# Sheet2.net
KiCad netlist of a schematic drawn in Altium Designer
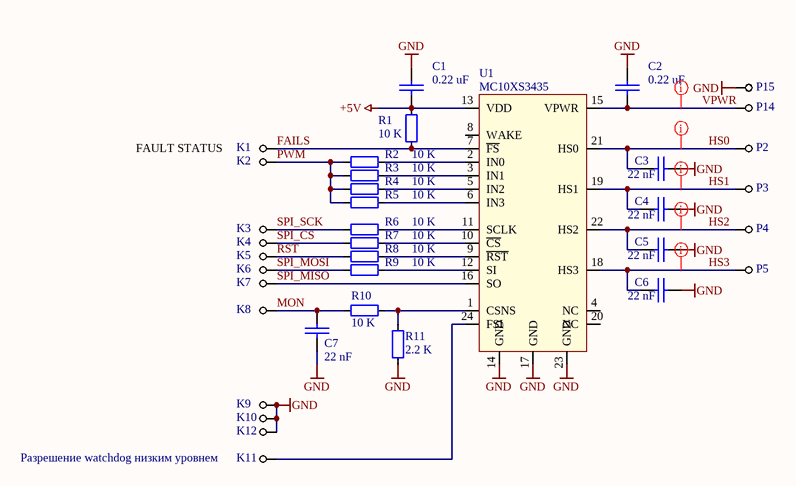
[diagram p0: Sheet2.SchDoc]

(export (version "E")
  (design (tool "Eeschema 10.0.6"))
  (components
    (comp (ref "C1")
      (value "0.22 uF")
      (footprint "2012[0805]")
      (description "0.22 uF, 50V, X7R,  0805")
      (fields (field (name "TOLERANCE") "+-10%") (field (name "MANUFACTURER") "Kemet"))
      (libsource (lib "ea_Capacitors") (part "C0805C224K5RACTU"))
    )
    (comp (ref "C2")
      (value "0.22 uF")
      (footprint "2012[0805]")
      (description "0.22 uF, 50V, X7R,  0805")
      (fields (field (name "TOLERANCE") "+-10%") (field (name "MANUFACTURER") "Kemet"))
      (libsource (lib "ea_Capacitors") (part "C0805C224K5RACTU"))
    )
    (comp (ref "C3")
      (value "22 nF")
      (footprint "1608[0603]")
      (description "22 nF, 50V, 10%, X7R, 0603 SMD MLC Capacitor")
      (fields (field (name "TOLERANCE") "10%") (field (name "MANUFACTURER") "SAMSUNG"))
      (libsource (lib "ea_Capacitors") (part "CL10B223KB8NNNC"))
    )
    (comp (ref "C4")
      (value "22 nF")
      (footprint "1608[0603]")
      (description "22 nF, 50V, 10%, X7R, 0603 SMD MLC Capacitor")
      (fields (field (name "TOLERANCE") "10%") (field (name "MANUFACTURER") "SAMSUNG"))
      (libsource (lib "ea_Capacitors") (part "CL10B223KB8NNNC"))
    )
    (comp (ref "C5")
      (value "22 nF")
      (footprint "1608[0603]")
      (description "22 nF, 50V, 10%, X7R, 0603 SMD MLC Capacitor")
      (fields (field (name "TOLERANCE") "10%") (field (name "MANUFACTURER") "SAMSUNG"))
      (libsource (lib "ea_Capacitors") (part "CL10B223KB8NNNC"))
    )
    (comp (ref "C6")
      (value "22 nF")
      (footprint "1608[0603]")
      (description "22 nF, 50V, 10%, X7R, 0603 SMD MLC Capacitor")
      (fields (field (name "TOLERANCE") "10%") (field (name "MANUFACTURER") "SAMSUNG"))
      (libsource (lib "ea_Capacitors") (part "CL10B223KB8NNNC"))
    )
    (comp (ref "C7")
      (value "22 nF")
      (footprint "1608[0603]")
      (description "22 nF, 50V, 10%, X7R, 0603 SMD MLC Capacitor")
      (fields (field (name "TOLERANCE") "10%") (field (name "MANUFACTURER") "SAMSUNG"))
      (libsource (lib "ea_Capacitors") (part "CL10B223KB8NNNC"))
    )
    (comp (ref "K1")
      (value "Pin 0.7 mm")
      (footprint "Mount hole 0.7 mm")
      (libsource (lib "ea_Connectors") (part "Pin 0.7 mm"))
    )
    (comp (ref "K2")
      (value "Pin 0.7 mm")
      (footprint "Mount hole 0.7 mm")
      (libsource (lib "ea_Connectors") (part "Pin 0.7 mm"))
    )
    (comp (ref "K3")
      (value "Pin 0.7 mm")
      (footprint "Mount hole 0.7 mm")
      (libsource (lib "ea_Connectors") (part "Pin 0.7 mm"))
    )
    (comp (ref "K4")
      (value "Pin 0.7 mm")
      (footprint "Mount hole 0.7 mm")
      (libsource (lib "ea_Connectors") (part "Pin 0.7 mm"))
    )
    (comp (ref "K5")
      (value "Pin 0.7 mm")
      (footprint "Mount hole 0.7 mm")
      (libsource (lib "ea_Connectors") (part "Pin 0.7 mm"))
    )
    (comp (ref "K6")
      (value "Pin 0.7 mm")
      (footprint "Mount hole 0.7 mm")
      (libsource (lib "ea_Connectors") (part "Pin 0.7 mm"))
    )
    (comp (ref "K7")
      (value "Pin 0.7 mm")
      (footprint "Mount hole 0.7 mm")
      (libsource (lib "ea_Connectors") (part "Pin 0.7 mm"))
    )
    (comp (ref "K8")
      (value "Pin 0.7 mm")
      (footprint "Mount hole 0.7 mm")
      (libsource (lib "ea_Connectors") (part "Pin 0.7 mm"))
    )
    (comp (ref "K9")
      (value "Pin 0.7 mm")
      (footprint "Mount hole 0.7 mm")
      (libsource (lib "ea_Connectors") (part "Pin 0.7 mm"))
    )
    (comp (ref "K10")
      (value "Pin 0.7 mm")
      (footprint "Mount hole 0.7 mm")
      (libsource (lib "ea_Connectors") (part "Pin 0.7 mm"))
    )
    (comp (ref "K11")
      (value "Pin 0.7 mm")
      (footprint "Mount hole 0.7 mm")
      (libsource (lib "ea_Connectors") (part "Pin 0.7 mm"))
    )
    (comp (ref "K12")
      (value "Pin 0.7 mm")
      (footprint "Mount hole 0.7 mm")
      (libsource (lib "ea_Connectors") (part "Pin 0.7 mm"))
    )
    (comp (ref "P2")
      (value "Pin 0.7 mm")
      (footprint "Mount hole 0.7 mm")
      (libsource (lib "ea_Connectors") (part "Pin 0.7 mm"))
    )
    (comp (ref "P3")
      (value "Pin 0.7 mm")
      (footprint "Mount hole 0.7 mm")
      (libsource (lib "ea_Connectors") (part "Pin 0.7 mm"))
    )
    (comp (ref "P4")
      (value "Pin 0.7 mm")
      (footprint "Mount hole 0.7 mm")
      (libsource (lib "ea_Connectors") (part "Pin 0.7 mm"))
    )
    (comp (ref "P5")
      (value "Pin 0.7 mm")
      (footprint "Mount hole 0.7 mm")
      (libsource (lib "ea_Connectors") (part "Pin 0.7 mm"))
    )
    (comp (ref "P14")
      (value "Pin 0.7 mm")
      (footprint "Mount hole 0.7 mm")
      (libsource (lib "ea_Connectors") (part "Pin 0.7 mm"))
    )
    (comp (ref "P15")
      (value "Pin 0.7 mm")
      (footprint "Mount hole 0.7 mm")
      (libsource (lib "ea_Connectors") (part "Pin 0.7 mm"))
    )
    (comp (ref "R1")
      (value "10 K")
      (footprint "0603")
      (description "10 K, 1%, 0603, SMD Resistor, Taped")
      (fields (field (name "MANUFACTURER") "PANASONIC") (field (name "TOLERANCE") "1%"))
      (libsource (lib "") (part "RL0603K010-1_1_1"))
    )
    (comp (ref "R2")
      (value "10 K")
      (footprint "0603")
      (description "10 K, 1%, 0603, SMD Resistor, Taped")
      (fields (field (name "MANUFACTURER") "PANASONIC") (field (name "TOLERANCE") "1%"))
      (libsource (lib "ea_Resistors") (part "RL0603K010-1_1"))
    )
    (comp (ref "R3")
      (value "10 K")
      (footprint "0603")
      (description "10 K, 1%, 0603, SMD Resistor, Taped")
      (fields (field (name "MANUFACTURER") "PANASONIC") (field (name "TOLERANCE") "1%"))
      (libsource (lib "ea_Resistors") (part "RL0603K010-1_1"))
    )
    (comp (ref "R4")
      (value "10 K")
      (footprint "0603")
      (description "10 K, 1%, 0603, SMD Resistor, Taped")
      (fields (field (name "MANUFACTURER") "PANASONIC") (field (name "TOLERANCE") "1%"))
      (libsource (lib "ea_Resistors") (part "RL0603K010-1_1"))
    )
    (comp (ref "R5")
      (value "10 K")
      (footprint "0603")
      (description "10 K, 1%, 0603, SMD Resistor, Taped")
      (fields (field (name "MANUFACTURER") "PANASONIC") (field (name "TOLERANCE") "1%"))
      (libsource (lib "ea_Resistors") (part "RL0603K010-1_1"))
    )
    (comp (ref "R6")
      (value "10 K")
      (footprint "0603")
      (description "10 K, 1%, 0603, SMD Resistor, Taped")
      (fields (field (name "MANUFACTURER") "PANASONIC") (field (name "TOLERANCE") "1%"))
      (libsource (lib "ea_Resistors") (part "RL0603K010-1_1"))
    )
    (comp (ref "R7")
      (value "10 K")
      (footprint "0603")
      (description "10 K, 1%, 0603, SMD Resistor, Taped")
      (fields (field (name "MANUFACTURER") "PANASONIC") (field (name "TOLERANCE") "1%"))
      (libsource (lib "ea_Resistors") (part "RL0603K010-1_1"))
    )
    (comp (ref "R8")
      (value "10 K")
      (footprint "0603")
      (description "10 K, 1%, 0603, SMD Resistor, Taped")
      (fields (field (name "MANUFACTURER") "PANASONIC") (field (name "TOLERANCE") "1%"))
      (libsource (lib "ea_Resistors") (part "RL0603K010-1_1"))
    )
    (comp (ref "R9")
      (value "10 K")
      (footprint "0603")
      (description "10 K, 1%, 0603, SMD Resistor, Taped")
      (fields (field (name "MANUFACTURER") "PANASONIC") (field (name "TOLERANCE") "1%"))
      (libsource (lib "ea_Resistors") (part "RL0603K010-1_1"))
    )
    (comp (ref "R10")
      (value "10 K")
      (footprint "0603")
      (description "10 K, 1%, 0603, SMD Resistor, Taped")
      (fields (field (name "MANUFACTURER") "PANASONIC") (field (name "TOLERANCE") "1%"))
      (libsource (lib "ea_Resistors") (part "RL0603K010-1_1"))
    )
    (comp (ref "R11")
      (value "2.2 K")
      (footprint "0603")
      (description "2.2 K, 1%, 0603, SMD Resistor, Taped")
      (fields (field (name "MANUFACTURER") "YAGEO AMERICA CORPORATION") (field (name "TOLERANCE") "1%"))
      (libsource (lib "ea_Resistors") (part "RL0603K002.2-1_1"))
    )
    (comp (ref "U1")
      (value "MC10XS3435")
      (footprint "24-PIN PQFN (12*12)")
      (description "Quad High-side Switch, -40..+125C, 24 PQFN")
      (fields (field (name "MANUFACTURER") "Freescale"))
      (libsource (lib "ea_IC_Interfaces") (part "MC10XS3435"))
    )
  )
  (nets
    (net (code "1") (name "+5V") (class "Default")
      (node (ref "C1") (pin "2") (pinfunction "2_2") (pintype "passive"))
      (node (ref "R1") (pin "1") (pinfunction "1_1") (pintype "passive"))
      (node (ref "U1") (pin "13") (pinfunction "VDD_13") (pintype "passive"))
    )
    (net (code "2") (name "/FAILS") (class "Default")
      (node (ref "K1") (pin "1") (pinfunction "1_1") (pintype "passive"))
      (node (ref "R1") (pin "2") (pinfunction "2_2") (pintype "passive"))
      (node (ref "U1") (pin "7") (pinfunction "~{FS}_7") (pintype "passive"))
    )
    (net (code "3") (name "/HS0") (class "Default")
      (node (ref "C3") (pin "1") (pinfunction "1_1") (pintype "passive"))
      (node (ref "P2") (pin "1") (pinfunction "1_1") (pintype "passive"))
      (node (ref "U1") (pin "21") (pinfunction "HS0_21") (pintype "passive"))
    )
    (net (code "4") (name "/HS1") (class "Default")
      (node (ref "C4") (pin "1") (pinfunction "1_1") (pintype "passive"))
      (node (ref "P3") (pin "1") (pinfunction "1_1") (pintype "passive"))
      (node (ref "U1") (pin "19") (pinfunction "HS1_19") (pintype "passive"))
    )
    (net (code "5") (name "/HS2") (class "Default")
      (node (ref "C5") (pin "1") (pinfunction "1_1") (pintype "passive"))
      (node (ref "P4") (pin "1") (pinfunction "1_1") (pintype "passive"))
      (node (ref "U1") (pin "22") (pinfunction "HS2_22") (pintype "passive"))
    )
    (net (code "6") (name "/HS3") (class "Default")
      (node (ref "C6") (pin "1") (pinfunction "1_1") (pintype "passive"))
      (node (ref "P5") (pin "1") (pinfunction "1_1") (pintype "passive"))
      (node (ref "U1") (pin "18") (pinfunction "HS3_18") (pintype "passive"))
    )
    (net (code "7") (name "/MON") (class "Default")
      (node (ref "C7") (pin "1") (pinfunction "1_1") (pintype "passive"))
      (node (ref "K8") (pin "1") (pinfunction "1_1") (pintype "passive"))
      (node (ref "R10") (pin "2") (pinfunction "2_2") (pintype "passive"))
    )
    (net (code "8") (name "/PWM") (class "Default")
      (node (ref "K2") (pin "1") (pinfunction "1_1") (pintype "passive"))
      (node (ref "R2") (pin "2") (pinfunction "2_2") (pintype "passive"))
      (node (ref "R3") (pin "2") (pinfunction "2_2") (pintype "passive"))
      (node (ref "R4") (pin "2") (pinfunction "2_2") (pintype "passive"))
      (node (ref "R5") (pin "2") (pinfunction "2_2") (pintype "passive"))
    )
    (net (code "9") (name "/RST") (class "Default")
      (node (ref "K5") (pin "1") (pinfunction "1_1") (pintype "passive"))
      (node (ref "R8") (pin "2") (pinfunction "2_2") (pintype "passive"))
    )
    (net (code "10") (name "/SPI_CS") (class "Default")
      (node (ref "K4") (pin "1") (pinfunction "1_1") (pintype "passive"))
      (node (ref "R7") (pin "2") (pinfunction "2_2") (pintype "passive"))
    )
    (net (code "11") (name "/SPI_MISO") (class "Default")
      (node (ref "K7") (pin "1") (pinfunction "1_1") (pintype "passive"))
      (node (ref "U1") (pin "16") (pinfunction "SO_16") (pintype "passive"))
    )
    (net (code "12") (name "/SPI_MOSI") (class "Default")
      (node (ref "K6") (pin "1") (pinfunction "1_1") (pintype "passive"))
      (node (ref "R9") (pin "2") (pinfunction "2_2") (pintype "passive"))
    )
    (net (code "13") (name "/SPI_SCK") (class "Default")
      (node (ref "K3") (pin "1") (pinfunction "1_1") (pintype "passive"))
      (node (ref "R6") (pin "2") (pinfunction "2_2") (pintype "passive"))
    )
    (net (code "14") (name "/VPWR") (class "Default")
      (node (ref "C2") (pin "2") (pinfunction "2_2") (pintype "passive"))
      (node (ref "P14") (pin "1") (pinfunction "1_1") (pintype "passive"))
      (node (ref "U1") (pin "15") (pinfunction "VPWR_15") (pintype "passive"))
    )
    (net (code "15") (name "GND") (class "Default")
      (node (ref "C1") (pin "1") (pinfunction "1_1") (pintype "passive"))
      (node (ref "C2") (pin "1") (pinfunction "1_1") (pintype "passive"))
      (node (ref "C3") (pin "2") (pinfunction "2_2") (pintype "passive"))
      (node (ref "C4") (pin "2") (pinfunction "2_2") (pintype "passive"))
      (node (ref "C5") (pin "2") (pinfunction "2_2") (pintype "passive"))
      (node (ref "C6") (pin "2") (pinfunction "2_2") (pintype "passive"))
      (node (ref "C7") (pin "2") (pinfunction "2_2") (pintype "passive"))
      (node (ref "K10") (pin "1") (pinfunction "1_1") (pintype "passive"))
      (node (ref "K12") (pin "1") (pinfunction "1_1") (pintype "passive"))
      (node (ref "K9") (pin "1") (pinfunction "1_1") (pintype "passive"))
      (node (ref "P15") (pin "1") (pinfunction "1_1") (pintype "passive"))
      (node (ref "R11") (pin "2") (pinfunction "2_2") (pintype "passive"))
      (node (ref "U1") (pin "14") (pinfunction "GND_14") (pintype "passive"))
      (node (ref "U1") (pin "17") (pinfunction "GND_17") (pintype "passive"))
      (node (ref "U1") (pin "23") (pinfunction "GND_23") (pintype "passive"))
    )
    (net (code "16") (name "Net-(U1-CSNS)") (class "Default")
      (node (ref "R10") (pin "1") (pinfunction "1_1") (pintype "passive"))
      (node (ref "R11") (pin "1") (pinfunction "1_1") (pintype "passive"))
      (node (ref "U1") (pin "1") (pinfunction "CSNS_1") (pintype "passive"))
    )
    (net (code "17") (name "Net-(U1-FSI)") (class "Default")
      (node (ref "K11") (pin "1") (pinfunction "1_1") (pintype "passive"))
      (node (ref "U1") (pin "24") (pinfunction "FSI_24") (pintype "passive"))
    )
    (net (code "18") (name "Net-(U1-IN0)") (class "Default")
      (node (ref "R2") (pin "1") (pinfunction "1_1") (pintype "passive"))
      (node (ref "U1") (pin "2") (pinfunction "IN0_2") (pintype "passive"))
    )
    (net (code "19") (name "Net-(U1-IN1)") (class "Default")
      (node (ref "R3") (pin "1") (pinfunction "1_1") (pintype "passive"))
      (node (ref "U1") (pin "3") (pinfunction "IN1_3") (pintype "passive"))
    )
    (net (code "20") (name "Net-(U1-IN2)") (class "Default")
      (node (ref "R4") (pin "1") (pinfunction "1_1") (pintype "passive"))
      (node (ref "U1") (pin "5") (pinfunction "IN2_5") (pintype "passive"))
    )
    (net (code "21") (name "Net-(U1-IN3)") (class "Default")
      (node (ref "R5") (pin "1") (pinfunction "1_1") (pintype "passive"))
      (node (ref "U1") (pin "6") (pinfunction "IN3_6") (pintype "passive"))
    )
    (net (code "22") (name "Net-(U1-SCLK)") (class "Default")
      (node (ref "R6") (pin "1") (pinfunction "1_1") (pintype "passive"))
      (node (ref "U1") (pin "11") (pinfunction "SCLK_11") (pintype "passive"))
    )
    (net (code "23") (name "Net-(U1-SI)") (class "Default")
      (node (ref "R9") (pin "1") (pinfunction "1_1") (pintype "passive"))
      (node (ref "U1") (pin "12") (pinfunction "SI_12") (pintype "passive"))
    )
    (net (code "24") (name "Net-(U1-~{CS})") (class "Default")
      (node (ref "R7") (pin "1") (pinfunction "1_1") (pintype "passive"))
      (node (ref "U1") (pin "10") (pinfunction "~{CS}_10") (pintype "passive"))
    )
    (net (code "25") (name "Net-(U1-~{RST})") (class "Default")
      (node (ref "R8") (pin "1") (pinfunction "1_1") (pintype "passive"))
      (node (ref "U1") (pin "9") (pinfunction "~{RST}_9") (pintype "passive"))
    )
    (net (code "26") (name "unconnected-(U1-NC-Pad4)") (class "Default")
      (node (ref "U1") (pin "4") (pinfunction "NC_4") (pintype "passive"))
    )
    (net (code "27") (name "unconnected-(U1-NC-Pad20)") (class "Default")
      (node (ref "U1") (pin "20") (pinfunction "NC_20") (pintype "passive"))
    )
    (net (code "28") (name "unconnected-(U1-WAKE-Pad8)") (class "Default")
      (node (ref "U1") (pin "8") (pinfunction "WAKE_8") (pintype "passive"))
    )
  )
)
